# main.net
KiCad netlist of a schematic drawn in EAGLE
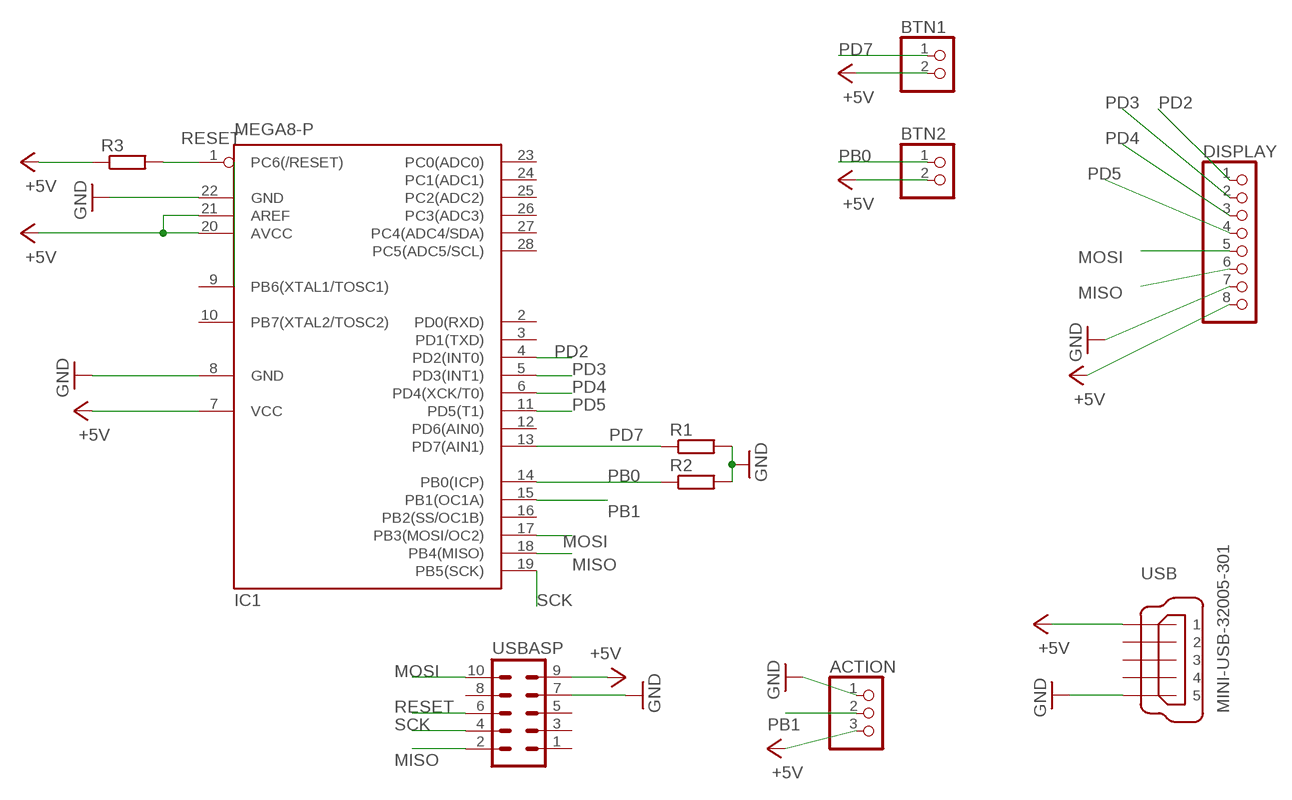
[diagram p0: schematic, sheet 1]

(export (version "E")
  (design (tool "Eeschema 10.0.6"))
  (components
    (comp (ref "ACTION")
      (value "PINHD-1X3")
      (footprint "eagle-import:1X03")
      (libsource (lib "eagle-import") (part "PINHD-1X3"))
    )
    (comp (ref "BTN1")
      (value "PINHD-1X2")
      (footprint "eagle-import:1X02")
      (libsource (lib "eagle-import") (part "PINHD-1X2"))
    )
    (comp (ref "BTN2")
      (value "PINHD-1X2")
      (footprint "eagle-import:1X02")
      (libsource (lib "eagle-import") (part "PINHD-1X2"))
    )
    (comp (ref "DISPLAY")
      (value "PINHD-1X8")
      (footprint "eagle-import:1X08")
      (libsource (lib "eagle-import") (part "PINHD-1X8"))
    )
    (comp (ref "IC1")
      (value "MEGA8-P")
      (footprint "eagle-import:DIL28-3")
      (libsource (lib "eagle-import") (part "MEGA8-P"))
    )
    (comp (ref "R1")
      (value "R-EU_0207/7")
      (footprint "eagle-import:0207_7")
      (libsource (lib "eagle-import") (part "R-EU_0207/7"))
    )
    (comp (ref "R2")
      (value "R-EU_0207/7")
      (footprint "eagle-import:0207_7")
      (libsource (lib "eagle-import") (part "R-EU_0207/7"))
    )
    (comp (ref "R3")
      (value "R-EU_0207/7")
      (footprint "eagle-import:0207_7")
      (libsource (lib "eagle-import") (part "R-EU_0207/7"))
    )
    (comp (ref "USB")
      (value "MINI-USB-32005-301")
      (footprint "eagle-import:32005-301")
      (libsource (lib "eagle-import") (part "MINI-USB-32005-301"))
    )
    (comp (ref "USBASP")
      (value "MA05-2")
      (footprint "eagle-import:MA05-2")
      (libsource (lib "eagle-import") (part "MA05-2"))
    )
  )
  (nets
    (net (code "1") (name "+5V") (class "Default")
      (node (ref "ACTION") (pin "3") (pinfunction "3_3") (pintype "passive"))
      (node (ref "BTN1") (pin "2") (pinfunction "2_2") (pintype "passive"))
      (node (ref "BTN2") (pin "2") (pinfunction "2_2") (pintype "passive"))
      (node (ref "DISPLAY") (pin "8") (pinfunction "8_8") (pintype "passive"))
      (node (ref "IC1") (pin "20") (pinfunction "AVCC_20") (pintype "power_in"))
      (node (ref "IC1") (pin "21") (pinfunction "AREF_21") (pintype "passive"))
      (node (ref "IC1") (pin "7") (pinfunction "VCC_7") (pintype "power_in"))
      (node (ref "R3") (pin "1") (pinfunction "1_1") (pintype "passive"))
      (node (ref "USB") (pin "1") (pinfunction "1_1") (pintype "passive"))
      (node (ref "USBASP") (pin "9") (pinfunction "9_9") (pintype "passive"))
    )
    (net (code "2") (name "/MISO") (class "Default")
      (node (ref "DISPLAY") (pin "6") (pinfunction "6_6") (pintype "passive"))
      (node (ref "IC1") (pin "18") (pinfunction "PB4(MISO)_18") (pintype "bidirectional"))
      (node (ref "USBASP") (pin "2") (pinfunction "2_2") (pintype "passive"))
    )
    (net (code "3") (name "/MOSI") (class "Default")
      (node (ref "DISPLAY") (pin "5") (pinfunction "5_5") (pintype "passive"))
      (node (ref "IC1") (pin "17") (pinfunction "PB3(MOSI/OC2)_17") (pintype "bidirectional"))
      (node (ref "USBASP") (pin "10") (pinfunction "10_10") (pintype "passive"))
    )
    (net (code "4") (name "/PB0") (class "Default")
      (node (ref "BTN2") (pin "1") (pinfunction "1_1") (pintype "passive"))
      (node (ref "IC1") (pin "14") (pinfunction "PB0(ICP)_14") (pintype "bidirectional"))
      (node (ref "R2") (pin "1") (pinfunction "1_1") (pintype "passive"))
    )
    (net (code "5") (name "/PB1") (class "Default")
      (node (ref "ACTION") (pin "2") (pinfunction "2_2") (pintype "passive"))
      (node (ref "IC1") (pin "15") (pinfunction "PB1(OC1A)_15") (pintype "bidirectional"))
    )
    (net (code "6") (name "/PD2") (class "Default")
      (node (ref "DISPLAY") (pin "1") (pinfunction "1_1") (pintype "passive"))
      (node (ref "IC1") (pin "4") (pinfunction "PD2(INT0)_4") (pintype "bidirectional"))
    )
    (net (code "7") (name "/PD3") (class "Default")
      (node (ref "DISPLAY") (pin "2") (pinfunction "2_2") (pintype "passive"))
      (node (ref "IC1") (pin "5") (pinfunction "PD3(INT1)_5") (pintype "bidirectional"))
    )
    (net (code "8") (name "/PD4") (class "Default")
      (node (ref "DISPLAY") (pin "3") (pinfunction "3_3") (pintype "passive"))
      (node (ref "IC1") (pin "6") (pinfunction "PD4(XCK/T0)_6") (pintype "bidirectional"))
    )
    (net (code "9") (name "/PD5") (class "Default")
      (node (ref "DISPLAY") (pin "4") (pinfunction "4_4") (pintype "passive"))
      (node (ref "IC1") (pin "11") (pinfunction "PD5(T1)_11") (pintype "bidirectional"))
    )
    (net (code "10") (name "/PD7") (class "Default")
      (node (ref "BTN1") (pin "1") (pinfunction "1_1") (pintype "passive"))
      (node (ref "IC1") (pin "13") (pinfunction "PD7(AIN1)_13") (pintype "bidirectional"))
      (node (ref "R1") (pin "1") (pinfunction "1_1") (pintype "passive"))
    )
    (net (code "11") (name "/RESET") (class "Default")
      (node (ref "IC1") (pin "1") (pinfunction "PC6(/RESET)_1") (pintype "bidirectional"))
      (node (ref "R3") (pin "2") (pinfunction "2_2") (pintype "passive"))
      (node (ref "USBASP") (pin "6") (pinfunction "6_6") (pintype "passive"))
    )
    (net (code "12") (name "/SCK") (class "Default")
      (node (ref "IC1") (pin "19") (pinfunction "PB5(SCK)_19") (pintype "bidirectional"))
      (node (ref "USBASP") (pin "4") (pinfunction "4_4") (pintype "passive"))
    )
    (net (code "13") (name "GND") (class "Default")
      (node (ref "ACTION") (pin "1") (pinfunction "1_1") (pintype "passive"))
      (node (ref "DISPLAY") (pin "7") (pinfunction "7_7") (pintype "passive"))
      (node (ref "IC1") (pin "22") (pinfunction "GND_22") (pintype "power_in"))
      (node (ref "IC1") (pin "8") (pinfunction "GND_8") (pintype "power_in"))
      (node (ref "R1") (pin "2") (pinfunction "2_2") (pintype "passive"))
      (node (ref "R2") (pin "2") (pinfunction "2_2") (pintype "passive"))
      (node (ref "USB") (pin "5") (pinfunction "5_5") (pintype "passive"))
      (node (ref "USBASP") (pin "7") (pinfunction "7_7") (pintype "passive"))
    )
    (net (code "14") (name "unconnected-(IC1-PB2(SS{slash}OC1B)-Pad16)") (class "Default")
      (node (ref "IC1") (pin "16") (pinfunction "PB2(SS/OC1B)_16") (pintype "bidirectional"))
    )
    (net (code "15") (name "unconnected-(IC1-PB6(XTAL1{slash}TOSC1)-Pad9)") (class "Default")
      (node (ref "IC1") (pin "9") (pinfunction "PB6(XTAL1/TOSC1)_9") (pintype "bidirectional"))
    )
    (net (code "16") (name "unconnected-(IC1-PB7(XTAL2{slash}TOSC2)-Pad10)") (class "Default")
      (node (ref "IC1") (pin "10") (pinfunction "PB7(XTAL2/TOSC2)_10") (pintype "bidirectional"))
    )
    (net (code "17") (name "unconnected-(IC1-PC0(ADC0)-Pad23)") (class "Default")
      (node (ref "IC1") (pin "23") (pinfunction "PC0(ADC0)_23") (pintype "bidirectional"))
    )
    (net (code "18") (name "unconnected-(IC1-PC1(ADC1)-Pad24)") (class "Default")
      (node (ref "IC1") (pin "24") (pinfunction "PC1(ADC1)_24") (pintype "bidirectional"))
    )
    (net (code "19") (name "unconnected-(IC1-PC2(ADC2)-Pad25)") (class "Default")
      (node (ref "IC1") (pin "25") (pinfunction "PC2(ADC2)_25") (pintype "bidirectional"))
    )
    (net (code "20") (name "unconnected-(IC1-PC3(ADC3)-Pad26)") (class "Default")
      (node (ref "IC1") (pin "26") (pinfunction "PC3(ADC3)_26") (pintype "bidirectional"))
    )
    (net (code "21") (name "unconnected-(IC1-PC4(ADC4{slash}SDA)-Pad27)") (class "Default")
      (node (ref "IC1") (pin "27") (pinfunction "PC4(ADC4/SDA)_27") (pintype "bidirectional"))
    )
    (net (code "22") (name "unconnected-(IC1-PC5(ADC5{slash}SCL)-Pad28)") (class "Default")
      (node (ref "IC1") (pin "28") (pinfunction "PC5(ADC5/SCL)_28") (pintype "bidirectional"))
    )
    (net (code "23") (name "unconnected-(IC1-PD0(RXD)-Pad2)") (class "Default")
      (node (ref "IC1") (pin "2") (pinfunction "PD0(RXD)_2") (pintype "bidirectional"))
    )
    (net (code "24") (name "unconnected-(IC1-PD1(TXD)-Pad3)") (class "Default")
      (node (ref "IC1") (pin "3") (pinfunction "PD1(TXD)_3") (pintype "bidirectional"))
    )
    (net (code "25") (name "unconnected-(IC1-PD6(AIN0)-Pad12)") (class "Default")
      (node (ref "IC1") (pin "12") (pinfunction "PD6(AIN0)_12") (pintype "bidirectional"))
    )
    (net (code "26") (name "unconnected-(USB-Pad2)") (class "Default")
      (node (ref "USB") (pin "2") (pinfunction "2_2") (pintype "passive"))
    )
    (net (code "27") (name "unconnected-(USB-Pad3)") (class "Default")
      (node (ref "USB") (pin "3") (pinfunction "3_3") (pintype "passive"))
    )
    (net (code "28") (name "unconnected-(USB-Pad4)") (class "Default")
      (node (ref "USB") (pin "4") (pinfunction "4_4") (pintype "passive"))
    )
    (net (code "29") (name "unconnected-(USBASP-Pad1)") (class "Default")
      (node (ref "USBASP") (pin "1") (pinfunction "1_1") (pintype "passive"))
    )
    (net (code "30") (name "unconnected-(USBASP-Pad3)") (class "Default")
      (node (ref "USBASP") (pin "3") (pinfunction "3_3") (pintype "passive"))
    )
    (net (code "31") (name "unconnected-(USBASP-Pad5)") (class "Default")
      (node (ref "USBASP") (pin "5") (pinfunction "5_5") (pintype "passive"))
    )
    (net (code "32") (name "unconnected-(USBASP-Pad8)") (class "Default")
      (node (ref "USBASP") (pin "8") (pinfunction "8_8") (pintype "passive"))
    )
  )
)
